# ppc_serial.net
KiCad netlist of a schematic drawn in Altium Designer
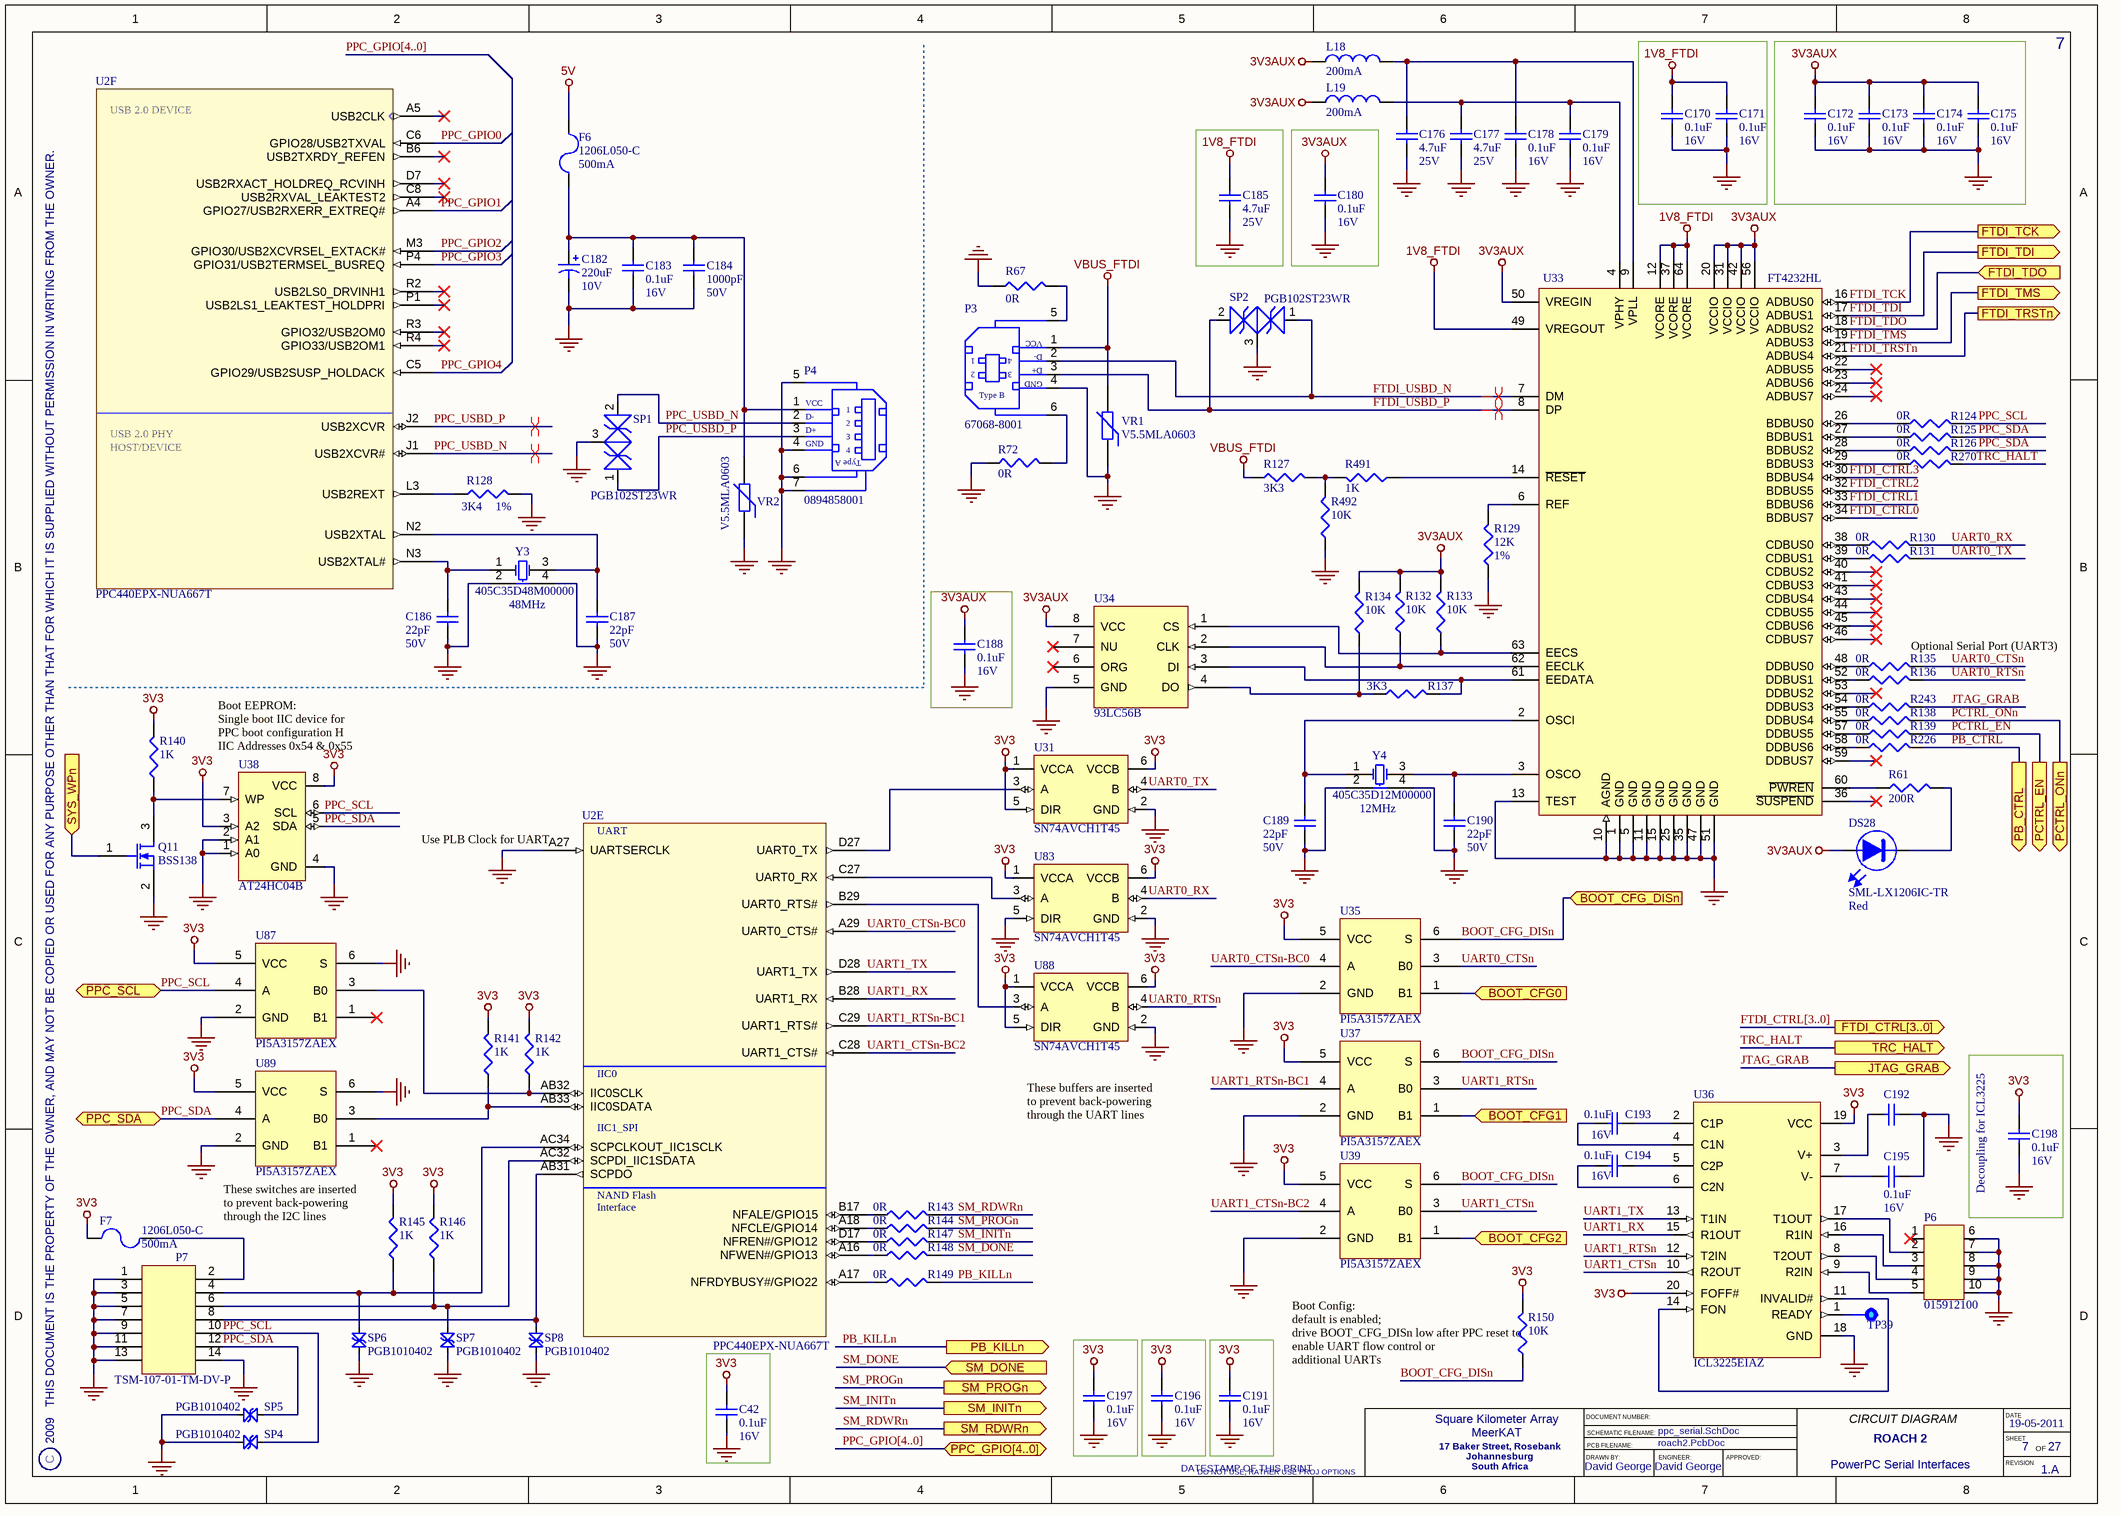
[diagram p0: ppc_serial.SchDoc]

(export (version "E")
  (design (tool "Eeschema 10.0.6"))
  (components
    (comp (ref "C42")
      (value "0.1uF")
      (footprint "CAPC1005X60L")
      (description "0.1uF, Ceramic Capacitor")
      (fields
        (field (name "RATING") "16V")
        (field (name "MANUFACTURER") "VENKEL")
        (field (name "PARTNUM") "C0402X7R160-104KN")
      )
      (libsource (lib "altium_db") (part "CapStd"))
    )
    (comp (ref "C170")
      (value "0.1uF")
      (footprint "CAPC1005X60L")
      (description "0.1uF, Ceramic Capacitor")
      (fields
        (field (name "RATING") "16V")
        (field (name "MANUFACTURER") "VENKEL")
        (field (name "PARTNUM") "C0402X7R160-104KN")
      )
      (libsource (lib "altium_db") (part "CapStd"))
    )
    (comp (ref "C171")
      (value "0.1uF")
      (footprint "CAPC1005X60L")
      (description "0.1uF, Ceramic Capacitor")
      (fields
        (field (name "RATING") "16V")
        (field (name "MANUFACTURER") "VENKEL")
        (field (name "PARTNUM") "C0402X7R160-104KN")
      )
      (libsource (lib "altium_db") (part "CapStd"))
    )
    (comp (ref "C172")
      (value "0.1uF")
      (footprint "CAPC1005X60L")
      (description "0.1uF, Ceramic Capacitor")
      (fields
        (field (name "RATING") "16V")
        (field (name "MANUFACTURER") "VENKEL")
        (field (name "PARTNUM") "C0402X7R160-104KN")
      )
      (libsource (lib "altium_db") (part "CapStd"))
    )
    (comp (ref "C173")
      (value "0.1uF")
      (footprint "CAPC1005X60L")
      (description "0.1uF, Ceramic Capacitor")
      (fields
        (field (name "RATING") "16V")
        (field (name "MANUFACTURER") "VENKEL")
        (field (name "PARTNUM") "C0402X7R160-104KN")
      )
      (libsource (lib "altium_db") (part "CapStd"))
    )
    (comp (ref "C174")
      (value "0.1uF")
      (footprint "CAPC1005X60L")
      (description "0.1uF, Ceramic Capacitor")
      (fields
        (field (name "RATING") "16V")
        (field (name "MANUFACTURER") "VENKEL")
        (field (name "PARTNUM") "C0402X7R160-104KN")
      )
      (libsource (lib "altium_db") (part "CapStd"))
    )
    (comp (ref "C175")
      (value "0.1uF")
      (footprint "CAPC1005X60L")
      (description "0.1uF, Ceramic Capacitor")
      (fields
        (field (name "RATING") "16V")
        (field (name "MANUFACTURER") "VENKEL")
        (field (name "PARTNUM") "C0402X7R160-104KN")
      )
      (libsource (lib "altium_db") (part "CapStd"))
    )
    (comp (ref "C176")
      (value "4.7uF")
      (footprint "CAPC2012X127L")
      (description "4.7uF, Ceramic Capacitor")
      (fields
        (field (name "RATING") "25V")
        (field (name "MANUFACTURER") "MURATA")
        (field (name "PARTNUM") "GRM21BR61E475KA12K")
      )
      (libsource (lib "altium_db") (part "CapStd"))
    )
    (comp (ref "C177")
      (value "4.7uF")
      (footprint "CAPC2012X127L")
      (description "4.7uF, Ceramic Capacitor")
      (fields
        (field (name "RATING") "25V")
        (field (name "MANUFACTURER") "MURATA")
        (field (name "PARTNUM") "GRM21BR61E475KA12K")
      )
      (libsource (lib "altium_db") (part "CapStd"))
    )
    (comp (ref "C178")
      (value "0.1uF")
      (footprint "CAPC1005X60L")
      (description "0.1uF, Ceramic Capacitor")
      (fields
        (field (name "RATING") "16V")
        (field (name "MANUFACTURER") "VENKEL")
        (field (name "PARTNUM") "C0402X7R160-104KN")
      )
      (libsource (lib "altium_db") (part "CapStd"))
    )
    (comp (ref "C179")
      (value "0.1uF")
      (footprint "CAPC1005X60L")
      (description "0.1uF, Ceramic Capacitor")
      (fields
        (field (name "RATING") "16V")
        (field (name "MANUFACTURER") "VENKEL")
        (field (name "PARTNUM") "C0402X7R160-104KN")
      )
      (libsource (lib "altium_db") (part "CapStd"))
    )
    (comp (ref "C180")
      (value "0.1uF")
      (footprint "CAPC1005X60L")
      (description "0.1uF, Ceramic Capacitor")
      (fields
        (field (name "RATING") "16V")
        (field (name "MANUFACTURER") "VENKEL")
        (field (name "PARTNUM") "C0402X7R160-104KN")
      )
      (libsource (lib "altium_db") (part "CapStd"))
    )
    (comp (ref "C182")
      (value "220uF")
      (footprint "CAPMP7343X430L")
      (description "220uF, Solid Tantalum Chip Capacitor")
      (fields
        (field (name "RATING") "10V")
        (field (name "MANUFACTURER") "KEMET")
        (field (name "PARTNUM") "T491X227M010AT")
      )
      (libsource (lib "altium_db") (part "CapPol"))
    )
    (comp (ref "C183")
      (value "0.1uF")
      (footprint "CAPC1005X60L")
      (description "0.1uF, Ceramic Capacitor")
      (fields
        (field (name "RATING") "16V")
        (field (name "MANUFACTURER") "VENKEL")
        (field (name "PARTNUM") "C0402X7R160-104KN")
      )
      (libsource (lib "altium_db") (part "CapStd"))
    )
    (comp (ref "C184")
      (value "1000pF")
      (footprint "CAPC1005X55L")
      (description "1000pF, Ceramic Capacitor")
      (fields
        (field (name "RATING") "50V")
        (field (name "MANUFACTURER") "MURATA")
        (field (name "PARTNUM") "GRM155R61H102KA01D")
      )
      (libsource (lib "altium_db") (part "CapStd"))
    )
    (comp (ref "C185")
      (value "4.7uF")
      (footprint "CAPC2012X127L")
      (description "4.7uF, Ceramic Capacitor")
      (fields
        (field (name "RATING") "25V")
        (field (name "MANUFACTURER") "MURATA")
        (field (name "PARTNUM") "GRM21BR61E475KA12K")
      )
      (libsource (lib "altium_db") (part "CapStd"))
    )
    (comp (ref "C186")
      (value "22pF")
      (footprint "CAPC1005X55L")
      (description "22pF, Ceramic Capacitor")
      (fields
        (field (name "RATING") "50V")
        (field (name "MANUFACTURER") "MURATA")
        (field (name "PARTNUM") "GRM1555C1H220JA01D")
      )
      (libsource (lib "altium_db") (part "CapStd"))
    )
    (comp (ref "C187")
      (value "22pF")
      (footprint "CAPC1005X55L")
      (description "22pF, Ceramic Capacitor")
      (fields
        (field (name "RATING") "50V")
        (field (name "MANUFACTURER") "MURATA")
        (field (name "PARTNUM") "GRM1555C1H220JA01D")
      )
      (libsource (lib "altium_db") (part "CapStd"))
    )
    (comp (ref "C188")
      (value "0.1uF")
      (footprint "CAPC1005X60L")
      (description "0.1uF, Ceramic Capacitor")
      (fields
        (field (name "RATING") "16V")
        (field (name "MANUFACTURER") "VENKEL")
        (field (name "PARTNUM") "C0402X7R160-104KN")
      )
      (libsource (lib "altium_db") (part "CapStd"))
    )
    (comp (ref "C189")
      (value "22pF")
      (footprint "CAPC1005X55L")
      (description "22pF, Ceramic Capacitor")
      (fields
        (field (name "RATING") "50V")
        (field (name "MANUFACTURER") "MURATA")
        (field (name "PARTNUM") "GRM1555C1H220JA01D")
      )
      (libsource (lib "altium_db") (part "CapStd"))
    )
    (comp (ref "C190")
      (value "22pF")
      (footprint "CAPC1005X55L")
      (description "22pF, Ceramic Capacitor")
      (fields
        (field (name "RATING") "50V")
        (field (name "MANUFACTURER") "MURATA")
        (field (name "PARTNUM") "GRM1555C1H220JA01D")
      )
      (libsource (lib "altium_db") (part "CapStd"))
    )
    (comp (ref "C191")
      (value "0.1uF")
      (footprint "CAPC1005X60L")
      (description "0.1uF, Ceramic Capacitor")
      (fields
        (field (name "RATING") "16V")
        (field (name "MANUFACTURER") "VENKEL")
        (field (name "PARTNUM") "C0402X7R160-104KN")
      )
      (libsource (lib "altium_db") (part "CapStd"))
    )
    (comp (ref "C192")
      (value "~")
      (footprint "CAPC1005X60L")
      (description "0.1uF, Ceramic Capacitor")
      (fields (field (name "MANUFACTURER") "VENKEL") (field (name "PARTNUM") "C0402X7R160-104KN"))
      (libsource (lib "altium_db") (part "CapStd"))
    )
    (comp (ref "C193")
      (value "0.1uF")
      (footprint "CAPC1005X60L")
      (description "0.1uF, Ceramic Capacitor")
      (fields
        (field (name "RATING") "16V")
        (field (name "MANUFACTURER") "VENKEL")
        (field (name "PARTNUM") "C0402X7R160-104KN")
      )
      (libsource (lib "altium_db") (part "CapStd"))
    )
    (comp (ref "C194")
      (value "0.1uF")
      (footprint "CAPC1005X60L")
      (description "0.1uF, Ceramic Capacitor")
      (fields
        (field (name "RATING") "16V")
        (field (name "MANUFACTURER") "VENKEL")
        (field (name "PARTNUM") "C0402X7R160-104KN")
      )
      (libsource (lib "altium_db") (part "CapStd"))
    )
    (comp (ref "C195")
      (value "0.1uF")
      (footprint "CAPC1005X60L")
      (description "0.1uF, Ceramic Capacitor")
      (fields
        (field (name "RATING") "16V")
        (field (name "MANUFACTURER") "VENKEL")
        (field (name "PARTNUM") "C0402X7R160-104KN")
      )
      (libsource (lib "altium_db") (part "CapStd"))
    )
    (comp (ref "C196")
      (value "0.1uF")
      (footprint "CAPC1005X60L")
      (description "0.1uF, Ceramic Capacitor")
      (fields
        (field (name "RATING") "16V")
        (field (name "MANUFACTURER") "VENKEL")
        (field (name "PARTNUM") "C0402X7R160-104KN")
      )
      (libsource (lib "altium_db") (part "CapStd"))
    )
    (comp (ref "C197")
      (value "0.1uF")
      (footprint "CAPC1005X60L")
      (description "0.1uF, Ceramic Capacitor")
      (fields
        (field (name "RATING") "16V")
        (field (name "MANUFACTURER") "VENKEL")
        (field (name "PARTNUM") "C0402X7R160-104KN")
      )
      (libsource (lib "altium_db") (part "CapStd"))
    )
    (comp (ref "C198")
      (value "0.1uF")
      (footprint "CAPC1005X60L")
      (description "0.1uF, Ceramic Capacitor")
      (fields
        (field (name "RATING") "16V")
        (field (name "MANUFACTURER") "VENKEL")
        (field (name "PARTNUM") "C0402X7R160-104KN")
      )
      (libsource (lib "altium_db") (part "CapStd"))
    )
    (comp (ref "DS28")
      (value "SML-LX1206IC-TR")
      (footprint "LEDC3216X120N")
      (description "Red, Surface mount, LED, 1206")
      (fields (field (name "COLOUR") "Red") (field (name "MANUFACTURER") "LUMEX"))
      (libsource (lib "altium_db") (part "LEDSTD"))
    )
    (comp (ref "F6")
      (value "1206L050-C")
      (footprint "FUSMC3215X145")
      (description "Resettable, Surface mount Fuse")
      (fields
        (field (name "MANUFACTURER") "Littelfuse")
        (field (name "PARTNUM") "1206L050-C")
        (field (name "RATING") "500mA")
      )
      (libsource (lib "altium_db") (part "FuseStd"))
    )
    (comp (ref "F7")
      (value "1206L050-C")
      (footprint "FUSMC3215X145")
      (description "Resettable, Surface mount Fuse")
      (fields
        (field (name "MANUFACTURER") "Littelfuse")
        (field (name "PARTNUM") "1206L050-C")
        (field (name "RATING") "500mA")
      )
      (libsource (lib "altium_db") (part "FuseStd"))
    )
    (comp (ref "L18")
      (value "600R")
      (footprint "INDC2012X130L")
      (description "600 Ohm, Chip Ferrite Bead")
      (fields
        (field (name "MANUFACTURER") "Murata")
        (field (name "PARTNUM") "BLM21BD601SN1")
        (field (name "RATING") "200mA")
      )
      (libsource (lib "altium_db") (part "IndStd"))
    )
    (comp (ref "L19")
      (value "600R")
      (footprint "INDC2012X130L")
      (description "600 Ohm, Chip Ferrite Bead")
      (fields
        (field (name "MANUFACTURER") "Murata")
        (field (name "PARTNUM") "BLM21BD601SN1")
        (field (name "RATING") "200mA")
      )
      (libsource (lib "altium_db") (part "IndStd"))
    )
    (comp (ref "P3")
      (value "67068-8001")
      (footprint "MOLEX_67068-8001")
      (description "Right angle, Through-hole, USB Type B Receptacle")
      (fields (field (name "PARTNUM") "67068-8001") (field (name "MANUFACTURER") "Molex"))
      (libsource (lib "altium_db") (part "USB_TYPE_B_GENERIC"))
    )
    (comp (ref "P4")
      (value "USB_TYPEA_TYCO")
      (footprint "MOLEX_0894858001")
      (description "Right angle, Through-hole, USB Type A Receptacle")
      (fields (field (name "PARTNUM") "0894858001"))
      (libsource (lib "altium_db") (part "0894858001"))
    )
    (comp (ref "P6")
      (value "015912100")
      (footprint "MOLEX_0015912100")
      (description "2x5, 2.54 mm Pitch, Male Header")
      (fields (field (name "MANUFACTURER") "Molex") (field (name "PARTNUM") "015912100"))
      (libsource (lib "altium_db") (part "con_hdr_2x5"))
    )
    (comp (ref "P7")
      (value "TSM-107-01-TM-DV-P")
      (footprint "SAMTEC_TSM-107-01-TM-DV-P")
      (description "2x7, 2.54 mm Pitch, Male Header")
      (fields (field (name "PARTNUM") "TSM-107-01-TM-DV-P") (field (name "MANUFACTURER") "SAMTEC"))
      (libsource (lib "altium_db") (part "con_hdr_2x7"))
    )
    (comp (ref "Q11")
      (value "BSS138")
      (footprint "SOT95P245X110-3N")
      (description "N-Channel Logic Level Enhancement Mode Field Effect Transistor")
      (fields (field (name "MANUFACTURER") "Fairchild Semiconductor"))
      (libsource (lib "altium_db") (part "BSS138"))
    )
    (comp (ref "R61")
      (value "200R")
      (footprint "RESC1005X40L")
      (description "200R, 1.1mm x 0.5mm, Thick Film Resistor")
      (fields (field (name "MANUFACTURER") "ROYALOHM") (field (name "PARTNUM") "0402WGF0201T1E"))
      (libsource (lib "altium_db") (part "ResStd"))
    )
    (comp (ref "R67")
      (value "0R")
      (footprint "RESC1005X40L")
      (description "0R, 1.1mm x 0.5mm, Thick Film Resistor")
      (fields (field (name "MANUFACTURER") "ROYALOHM") (field (name "PARTNUM") "0402WG00000T1E"))
      (libsource (lib "altium_db") (part "ResStd"))
    )
    (comp (ref "R72")
      (value "0R")
      (footprint "RESC1005X40L")
      (description "0R, 1.1mm x 0.5mm, Thick Film Resistor")
      (fields (field (name "MANUFACTURER") "ROYALOHM") (field (name "PARTNUM") "0402WG00000T1E"))
      (libsource (lib "altium_db") (part "ResStd"))
    )
    (comp (ref "R124")
      (value "0R")
      (footprint "RESC1005X40L")
      (description "0R, 1.1mm x 0.5mm, Thick Film Resistor")
      (fields (field (name "MANUFACTURER") "ROYALOHM") (field (name "PARTNUM") "0402WG00000T1E"))
      (libsource (lib "altium_db") (part "ResStd"))
    )
    (comp (ref "R125")
      (value "0R")
      (footprint "RESC1005X40L")
      (description "0R, 1.1mm x 0.5mm, Thick Film Resistor")
      (fields (field (name "MANUFACTURER") "ROYALOHM") (field (name "PARTNUM") "0402WG00000T1E"))
      (libsource (lib "altium_db") (part "ResStd"))
    )
    (comp (ref "R126")
      (value "0R")
      (footprint "RESC1005X40L")
      (description "0R, 1.1mm x 0.5mm, Thick Film Resistor")
      (fields (field (name "MANUFACTURER") "ROYALOHM") (field (name "PARTNUM") "0402WG00000T1E"))
      (libsource (lib "altium_db") (part "ResStd"))
    )
    (comp (ref "R127")
      (value "3K3")
      (footprint "RESC1005X40L")
      (description "3K3, 1.1mm x 0.5mm, Thick Film Resistor")
      (fields (field (name "MANUFACTURER") "ROYALOHM") (field (name "PARTNUM") "0402WGJ0332T1E"))
      (libsource (lib "altium_db") (part "ResStd"))
    )
    (comp (ref "R128")
      (value "3K4")
      (footprint "RESC1005X40L")
      (description "3K4, 1.1mm x 0.5mm, Thick Film Resistor")
      (fields
        (field (name "MANUFACTURER") "ROYALOHM")
        (field (name "PARTNUM") "0402WGF0342T1E")
        (field (name "TOLERANCE") "1%")
      )
      (libsource (lib "altium_db") (part "ResStd"))
    )
    (comp (ref "R129")
      (value "12K")
      (footprint "RESC1005X40L")
      (description "12K, 1.1mm x 0.5mm, Thick Film Resistor")
      (fields
        (field (name "MANUFACTURER") "ROYALOHM")
        (field (name "PARTNUM") "0402WGF0123T1E")
        (field (name "TOLERANCE") "1%")
      )
      (libsource (lib "altium_db") (part "ResStd"))
    )
    (comp (ref "R130")
      (value "0R")
      (footprint "RESC1005X40L")
      (description "0R, 1.1mm x 0.5mm, Thick Film Resistor")
      (fields (field (name "MANUFACTURER") "ROYALOHM") (field (name "PARTNUM") "0402WG00000T1E"))
      (libsource (lib "altium_db") (part "ResStd"))
    )
    (comp (ref "R131")
      (value "0R")
      (footprint "RESC1005X40L")
      (description "0R, 1.1mm x 0.5mm, Thick Film Resistor")
      (fields (field (name "MANUFACTURER") "ROYALOHM") (field (name "PARTNUM") "0402WG00000T1E"))
      (libsource (lib "altium_db") (part "ResStd"))
    )
    (comp (ref "R132")
      (value "10K")
      (footprint "RESC1005X40L")
      (description "10K, 1.1mm x 0.5mm, Thick Film Resistor")
      (fields (field (name "MANUFACTURER") "ROYALOHM") (field (name "PARTNUM") "0402WGJ0103T1E"))
      (libsource (lib "altium_db") (part "ResStd"))
    )
    (comp (ref "R133")
      (value "10K")
      (footprint "RESC1005X40L")
      (description "10K, 1.1mm x 0.5mm, Thick Film Resistor")
      (fields (field (name "MANUFACTURER") "ROYALOHM") (field (name "PARTNUM") "0402WGJ0103T1E"))
      (libsource (lib "altium_db") (part "ResStd"))
    )
    (comp (ref "R134")
      (value "10K")
      (footprint "RESC1005X40L")
      (description "10K, 1.1mm x 0.5mm, Thick Film Resistor")
      (fields (field (name "MANUFACTURER") "ROYALOHM") (field (name "PARTNUM") "0402WGJ0103T1E"))
      (libsource (lib "altium_db") (part "ResStd"))
    )
    (comp (ref "R135")
      (value "0R")
      (footprint "RESC1005X40L")
      (description "0R, 1.1mm x 0.5mm, Thick Film Resistor")
      (fields (field (name "MANUFACTURER") "ROYALOHM") (field (name "PARTNUM") "0402WG00000T1E"))
      (libsource (lib "altium_db") (part "ResStd"))
    )
    (comp (ref "R136")
      (value "0R")
      (footprint "RESC1005X40L")
      (description "0R, 1.1mm x 0.5mm, Thick Film Resistor")
      (fields (field (name "MANUFACTURER") "ROYALOHM") (field (name "PARTNUM") "0402WG00000T1E"))
      (libsource (lib "altium_db") (part "ResStd"))
    )
    (comp (ref "R137")
      (value "3K3")
      (footprint "RESC1005X40L")
      (description "3K3, 1.1mm x 0.5mm, Thick Film Resistor")
      (fields (field (name "MANUFACTURER") "ROYALOHM") (field (name "PARTNUM") "0402WGJ0332T1E"))
      (libsource (lib "altium_db") (part "ResStd"))
    )
    (comp (ref "R138")
      (value "0R")
      (footprint "RESC1005X40L")
      (description "0R, 1.1mm x 0.5mm, Thick Film Resistor")
      (fields (field (name "MANUFACTURER") "ROYALOHM") (field (name "PARTNUM") "0402WG00000T1E"))
      (libsource (lib "altium_db") (part "ResStd"))
    )
    (comp (ref "R139")
      (value "0R")
      (footprint "RESC1005X40L")
      (description "0R, 1.1mm x 0.5mm, Thick Film Resistor")
      (fields (field (name "MANUFACTURER") "ROYALOHM") (field (name "PARTNUM") "0402WG00000T1E"))
      (libsource (lib "altium_db") (part "ResStd"))
    )
    (comp (ref "R140")
      (value "1K")
      (footprint "RESC1005X40L")
      (description "1K, 1.1mm x 0.5mm, Thick Film Resistor")
      (fields (field (name "MANUFACTURER") "ROYALOHM") (field (name "PARTNUM") "0402WGJ0102T1E"))
      (libsource (lib "altium_db") (part "ResStd"))
    )
    (comp (ref "R141")
      (value "1K")
      (footprint "RESC1005X40L")
      (description "1K, 1.1mm x 0.5mm, Thick Film Resistor")
      (fields (field (name "MANUFACTURER") "ROYALOHM") (field (name "PARTNUM") "0402WGJ0102T1E"))
      (libsource (lib "altium_db") (part "ResStd"))
    )
    (comp (ref "R142")
      (value "1K")
      (footprint "RESC1005X40L")
      (description "1K, 1.1mm x 0.5mm, Thick Film Resistor")
      (fields (field (name "MANUFACTURER") "ROYALOHM") (field (name "PARTNUM") "0402WGJ0102T1E"))
      (libsource (lib "altium_db") (part "ResStd"))
    )
    (comp (ref "R143")
      (value "0R")
      (footprint "RESC1005X40L")
      (description "0R, 1.1mm x 0.5mm, Thick Film Resistor")
      (fields (field (name "MANUFACTURER") "ROYALOHM") (field (name "PARTNUM") "0402WG00000T1E"))
      (libsource (lib "altium_db") (part "ResStd"))
    )
    (comp (ref "R144")
      (value "0R")
      (footprint "RESC1005X40L")
      (description "0R, 1.1mm x 0.5mm, Thick Film Resistor")
      (fields (field (name "MANUFACTURER") "ROYALOHM") (field (name "PARTNUM") "0402WG00000T1E"))
      (libsource (lib "altium_db") (part "ResStd"))
    )
    (comp (ref "R145")
      (value "1K")
      (footprint "RESC1005X40L")
      (description "1K, 1.1mm x 0.5mm, Thick Film Resistor")
      (fields (field (name "MANUFACTURER") "ROYALOHM") (field (name "PARTNUM") "0402WGJ0102T1E"))
      (libsource (lib "altium_db") (part "ResStd"))
    )
    (comp (ref "R146")
      (value "1K")
      (footprint "RESC1005X40L")
      (description "1K, 1.1mm x 0.5mm, Thick Film Resistor")
      (fields (field (name "MANUFACTURER") "ROYALOHM") (field (name "PARTNUM") "0402WGJ0102T1E"))
      (libsource (lib "altium_db") (part "ResStd"))
    )
    (comp (ref "R147")
      (value "0R")
      (footprint "RESC1005X40L")
      (description "0R, 1.1mm x 0.5mm, Thick Film Resistor")
      (fields (field (name "MANUFACTURER") "ROYALOHM") (field (name "PARTNUM") "0402WG00000T1E"))
      (libsource (lib "altium_db") (part "ResStd"))
    )
    (comp (ref "R148")
      (value "0R")
      (footprint "RESC1005X40L")
      (description "0R, 1.1mm x 0.5mm, Thick Film Resistor")
      (fields (field (name "MANUFACTURER") "ROYALOHM") (field (name "PARTNUM") "0402WG00000T1E"))
      (libsource (lib "altium_db") (part "ResStd"))
    )
    (comp (ref "R149")
      (value "0R")
      (footprint "RESC1005X40L")
      (description "0R, 1.1mm x 0.5mm, Thick Film Resistor")
      (fields (field (name "MANUFACTURER") "ROYALOHM") (field (name "PARTNUM") "0402WG00000T1E"))
      (libsource (lib "altium_db") (part "ResStd"))
    )
    (comp (ref "R150")
      (value "10K")
      (footprint "RESC1005X40L")
      (description "10K, 1.1mm x 0.5mm, Thick Film Resistor")
      (fields (field (name "MANUFACTURER") "ROYALOHM") (field (name "PARTNUM") "0402WGJ0103T1E"))
      (libsource (lib "altium_db") (part "ResStd"))
    )
    (comp (ref "R226")
      (value "0R")
      (footprint "RESC1005X40L")
      (description "0R, 1.1mm x 0.5mm, Thick Film Resistor")
      (fields (field (name "MANUFACTURER") "ROYALOHM") (field (name "PARTNUM") "0402WG00000T1E"))
      (libsource (lib "altium_db") (part "ResStd"))
    )
    (comp (ref "R243")
      (value "0R")
      (footprint "RESC1005X40L")
      (description "0R, 1.1mm x 0.5mm, Thick Film Resistor")
      (fields (field (name "MANUFACTURER") "ROYALOHM") (field (name "PARTNUM") "0402WG00000T1E"))
      (libsource (lib "altium_db") (part "ResStd"))
    )
    (comp (ref "R270")
      (value "0R")
      (footprint "RESC1005X40L")
      (description "0R, 1.1mm x 0.5mm, Thick Film Resistor")
      (fields (field (name "MANUFACTURER") "ROYALOHM") (field (name "PARTNUM") "0402WG00000T1E"))
      (libsource (lib "altium_db") (part "ResStd"))
    )
    (comp (ref "R491")
      (value "1K")
      (footprint "RESC1005X40L")
      (description "1K, 1.1mm x 0.5mm, Thick Film Resistor")
      (fields (field (name "MANUFACTURER") "ROYALOHM") (field (name "PARTNUM") "0402WGJ0102T1E"))
      (libsource (lib "altium_db") (part "ResStd"))
    )
    (comp (ref "R492")
      (value "10K")
      (footprint "RESC1005X40L")
      (description "10K, 1.1mm x 0.5mm, Thick Film Resistor")
      (fields (field (name "MANUFACTURER") "ROYALOHM") (field (name "PARTNUM") "0402WGJ0103T1E"))
      (libsource (lib "altium_db") (part "ResStd"))
    )
    (comp (ref "SP1")
      (value "PGB102ST23WR")
      (footprint "SOT95P245X110-3N")
      (description "Ultra-low Capacitance, Surface mount ESD Suppressor")
      (fields (field (name "PARTNUM") "PGB102ST23WR") (field (name "MANUFACTURER") "Littelfuse"))
      (libsource (lib "altium_db") (part "PGB002ST23WR"))
    )
    (comp (ref "SP2")
      (value "PGB102ST23WR")
      (footprint "SOT95P245X110-3N")
      (description "Ultra-low Capacitance, Surface mount ESD Suppressor")
      (fields (field (name "PARTNUM") "PGB102ST23WR") (field (name "MANUFACTURER") "Littelfuse"))
      (libsource (lib "altium_db") (part "PGB002ST23WR"))
    )
    (comp (ref "SP4")
      (value "PGB1010402")
      (footprint "PGB1010402")
      (description "Surface Mount Polymeric ESD Suppressor in an 0402 package")
      (fields (field (name "PARTNUM") "PGB1010402"))
      (libsource (lib "altium_db") (part "PGB1010402"))
    )
    (comp (ref "SP5")
      (value "PGB1010402")
      (footprint "PGB1010402")
      (description "Surface Mount Polymeric ESD Suppressor in an 0402 package")
      (fields (field (name "PARTNUM") "PGB1010402"))
      (libsource (lib "altium_db") (part "PGB1010402"))
    )
    (comp (ref "SP6")
      (value "PGB1010402")
      (footprint "PGB1010402")
      (description "Surface Mount Polymeric ESD Suppressor in an 0402 package")
      (fields (field (name "PARTNUM") "PGB1010402"))
      (libsource (lib "altium_db") (part "PGB1010402"))
    )
    (comp (ref "SP7")
      (value "PGB1010402")
      (footprint "PGB1010402")
      (description "Surface Mount Polymeric ESD Suppressor in an 0402 package")
      (fields (field (name "PARTNUM") "PGB1010402"))
      (libsource (lib "altium_db") (part "PGB1010402"))
    )
    (comp (ref "SP8")
      (value "PGB1010402")
      (footprint "PGB1010402")
      (description "Surface Mount Polymeric ESD Suppressor in an 0402 package")
      (fields (field (name "PARTNUM") "PGB1010402"))
      (libsource (lib "altium_db") (part "PGB1010402"))
    )
    (comp (ref "TP39")
      (value "Testpoint")
      (footprint "TP100")
      (description "1mm Diameter, through-hole, Circular Test-point")
      (libsource (lib "altium_db") (part "Testpoint"))
    )
    (comp (ref "U2")
      (value "PPC440EPX-NUA667T")
      (footprint "TE-PBGA680")
      (description "667MHz, non-RoHS, PPC440EPx uProcessor")
      (fields (field (name "MANUFACTURER") "Applied Micro"))
      (libsource (lib "altium_db") (part "PPC440EPX"))
    )
    (comp (ref "U31")
      (value "SN74AVCH1T45")
      (footprint "SOT23-6")
      (description "Single-Bit Dual Supply Bus Transceiver with Configurable Voltage Translation and 3-State Outputs")
      (fields (field (name "MANUFACTURER") "Texas Instruments"))
      (libsource (lib "altium_db") (part "SN74AVCH1T45"))
    )
    (comp (ref "U33")
      (value "FT4232HL")
      (footprint "QFN64")
      (description "Quad High Speed USB to Multipurpose UART/MPSSE")
      (fields (field (name "MANUFACTURER") "FTDI"))
      (libsource (lib "altium_db") (part "FT4232HL"))
    )
    (comp (ref "U34")
      (value "93LC56B")
      (footprint "SOIC150-8_N")
      (description "2K Microwire Compatible Serial EEPROM")
      (fields (field (name "MANUFACTURER") "Microchip") (field (name "PARTNUM") "93LC56B/SN"))
      (libsource (lib "altium_db") (part "93LC56B"))
    )
    (comp (ref "U35")
      (value "PI5A3157ZAEX")
      (footprint "SC70-6")
      (description "Low voltage SPDT Analogue Switch")
      (fields (field (name "MANUFACTURER") "PERICOM"))
      (libsource (lib "altium_db") (part "PI5A3157ZAEX"))
    )
    (comp (ref "U36")
      (value "ICL3225EIAZ")
      (footprint "SSOP20_M")
      (description "Low-power RS232 transceivers")
      (fields (field (name "MANUFACTURER") "Intersil"))
      (libsource (lib "altium_db") (part "ICL3225"))
    )
    (comp (ref "U37")
      (value "PI5A3157ZAEX")
      (footprint "SC70-6")
      (description "Low voltage SPDT Analogue Switch")
      (fields (field (name "MANUFACTURER") "PERICOM"))
      (libsource (lib "altium_db") (part "PI5A3157ZAEX"))
    )
    (comp (ref "U38")
      (value "AT24HC04B")
      (footprint "TSSOP-8A2")
      (description "4K Serial EEPROM")
      (fields (field (name "MANUFACTURER") "Atmel"))
      (libsource (lib "altium_db") (part "AT24HC04B"))
    )
    (comp (ref "U39")
      (value "PI5A3157ZAEX")
      (footprint "SC70-6")
      (description "Low voltage SPDT Analogue Switch")
      (fields (field (name "MANUFACTURER") "PERICOM"))
      (libsource (lib "altium_db") (part "PI5A3157ZAEX"))
    )
    (comp (ref "U83")
      (value "SN74AVCH1T45")
      (footprint "SOT23-6")
      (description "Single-Bit Dual Supply Bus Transceiver with Configurable Voltage Translation and 3-State Outputs")
      (fields (field (name "MANUFACTURER") "Texas Instruments"))
      (libsource (lib "altium_db") (part "SN74AVCH1T45"))
    )
    (comp (ref "U87")
      (value "PI5A3157ZAEX")
      (footprint "SC70-6")
      (description "Low voltage SPDT Analogue Switch")
      (fields (field (name "MANUFACTURER") "PERICOM"))
      (libsource (lib "altium_db") (part "PI5A3157ZAEX"))
    )
    (comp (ref "U88")
      (value "SN74AVCH1T45")
      (footprint "SOT23-6")
      (description "Single-Bit Dual Supply Bus Transceiver with Configurable Voltage Translation and 3-State Outputs")
      (fields (field (name "MANUFACTURER") "Texas Instruments"))
      (libsource (lib "altium_db") (part "SN74AVCH1T45"))
    )
    (comp (ref "U89")
      (value "PI5A3157ZAEX")
      (footprint "SC70-6")
      (description "Low voltage SPDT Analogue Switch")
      (fields (field (name "MANUFACTURER") "PERICOM"))
      (libsource (lib "altium_db") (part "PI5A3157ZAEX"))
    )
    (comp (ref "VR1")
      (value "V5.5MLA0603")
      (footprint "VAR_V5_5MLA0603")
      (description "Multilayer Transient Voltage Surge Suppressing Varistor")
      (fields (field (name "MANUFACTURER") "Littelfuse") (field (name "PARTNUM") "V5.5MLA0603"))
      (libsource (lib "altium_db") (part "Varistor"))
    )
    (comp (ref "VR2")
      (value "V5.5MLA0603")
      (footprint "VAR_V5_5MLA0603")
      (description "Multilayer Transient Voltage Surge Suppressing Varistor")
      (fields (field (name "MANUFACTURER") "Littelfuse") (field (name "PARTNUM") "V5.5MLA0603"))
      (libsource (lib "altium_db") (part "Varistor"))
    )
    (comp (ref "Y3")
      (value "405XXXXXXMXXXXX")
      (footprint "405XXXXXXMXXXXX")
      (description "48 MHz, Surface mount, Crystal Oscillator")
      (fields (field (name "PARTNUM") "405C35D48M00000") (field (name "FREQUENCY") "48MHz"))
      (libsource (lib "altium_db") (part "405XXXXXXMXXXXX"))
    )
    (comp (ref "Y4")
      (value "405C35D12M00000")
      (footprint "405XXXXXXMXXXXX")
      (description "12 MHz, Surface mount, Crystal Oscillator")
      (fields
        (field (name "PARTNUM") "405C35D12M00000")
        (field (name "FREQUENCY") "12MHz")
        (field (name "MANUFACTURER") "CTS")
      )
      (libsource (lib "altium_db") (part "405XXXXXXMXXXXX"))
    )
  )
  (nets
    (net (code "1") (name "/BOOT_CFG0") (class "Default")
      (node (ref "U35") (pin "1") (pinfunction "B1_1") (pintype "passive"))
    )
    (net (code "2") (name "/BOOT_CFG1") (class "Default")
      (node (ref "U37") (pin "1") (pinfunction "B1_1") (pintype "passive"))
    )
    (net (code "3") (name "/BOOT_CFG2") (class "Default")
      (node (ref "U39") (pin "1") (pinfunction "B1_1") (pintype "passive"))
    )
    (net (code "4") (name "/BOOT_CFG_DISn") (class "Default")
      (node (ref "R150") (pin "1") (pinfunction "1_1") (pintype "passive"))
      (node (ref "U35") (pin "6") (pinfunction "S_6") (pintype "passive"))
      (node (ref "U37") (pin "6") (pinfunction "S_6") (pintype "passive"))
      (node (ref "U39") (pin "6") (pinfunction "S_6") (pintype "passive"))
    )
    (net (code "5") (name "/FTDI_CTRL0") (class "Default")
      (node (ref "U33") (pin "34") (pinfunction "BDBUS7_34") (pintype "bidirectional"))
    )
    (net (code "6") (name "/FTDI_CTRL1") (class "Default")
      (node (ref "U33") (pin "33") (pinfunction "BDBUS6_33") (pintype "bidirectional"))
    )
    (net (code "7") (name "/FTDI_CTRL2") (class "Default")
      (node (ref "U33") (pin "32") (pinfunction "BDBUS5_32") (pintype "bidirectional"))
    )
    (net (code "8") (name "/FTDI_CTRL3") (class "Default")
      (node (ref "U33") (pin "30") (pinfunction "BDBUS4_30") (pintype "bidirectional"))
    )
    (net (code "10") (name "/FTDI_TCK") (class "Default")
      (node (ref "U33") (pin "16") (pinfunction "ADBUS0_16") (pintype "bidirectional"))
    )
    (net (code "11") (name "/FTDI_TDI") (class "Default")
      (node (ref "U33") (pin "17") (pinfunction "ADBUS1_17") (pintype "bidirectional"))
    )
    (net (code "12") (name "/FTDI_TDO") (class "Default")
      (node (ref "U33") (pin "18") (pinfunction "ADBUS2_18") (pintype "bidirectional"))
    )
    (net (code "13") (name "/FTDI_TMS") (class "Default")
      (node (ref "U33") (pin "19") (pinfunction "ADBUS3_19") (pintype "bidirectional"))
    )
    (net (code "14") (name "/FTDI_TRSTn") (class "Default")
      (node (ref "U33") (pin "21") (pinfunction "ADBUS4_21") (pintype "bidirectional"))
    )
    (net (code "15") (name "/FTDI_USBD_N") (class "Default")
      (node (ref "P3") (pin "2") (pinfunction "2_2") (pintype "bidirectional"))
      (node (ref "SP2") (pin "1") (pinfunction "A_1") (pintype "passive"))
      (node (ref "U33") (pin "7") (pinfunction "DM_7") (pintype "passive"))
    )
    (net (code "16") (name "/FTDI_USBD_P") (class "Default")
      (node (ref "P3") (pin "3") (pinfunction "3_3") (pintype "bidirectional"))
      (node (ref "SP2") (pin "2") (pinfunction "B_2") (pintype "passive"))
      (node (ref "U33") (pin "8") (pinfunction "DP_8") (pintype "passive"))
    )
    (net (code "17") (name "/JTAG_GRAB") (class "Default")
      (node (ref "R243") (pin "2") (pinfunction "2_2") (pintype "passive"))
    )
    (net (code "18") (name "/PB_CTRL") (class "Default")
      (node (ref "R226") (pin "2") (pinfunction "2_2") (pintype "passive"))
    )
    (net (code "19") (name "/PB_KILLn") (class "Default")
      (node (ref "R149") (pin "2") (pinfunction "2_2") (pintype "passive"))
    )
    (net (code "20") (name "/PCTRL_EN") (class "Default")
      (node (ref "R139") (pin "2") (pinfunction "2_2") (pintype "passive"))
    )
    (net (code "21") (name "/PCTRL_ONn") (class "Default")
      (node (ref "R138") (pin "2") (pinfunction "2_2") (pintype "passive"))
    )
    (net (code "22") (name "/PPC_GPIO0") (class "Default")
      (node (ref "U2") (pin "C6") (pinfunction "GPIO28/USB2TXVAL_C6") (pintype "input"))
    )
    (net (code "23") (name "/PPC_GPIO1") (class "Default")
      (node (ref "U2") (pin "A4") (pinfunction "GPIO27/USB2RXERR_EXTREQ#_A4") (pintype "output"))
    )
    (net (code "24") (name "/PPC_GPIO2") (class "Default")
      (node (ref "U2") (pin "M3") (pinfunction "GPIO30/USB2XCVRSEL_EXTACK#_M3") (pintype "input"))
    )
    (net (code "25") (name "/PPC_GPIO3") (class "Default")
      (node (ref "U2") (pin "P4") (pinfunction "GPIO31/USB2TERMSEL_BUSREQ_P4") (pintype "input"))
    )
    (net (code "26") (name "/PPC_GPIO4") (class "Default")
      (node (ref "U2") (pin "C5") (pinfunction "GPIO29/USB2SUSP_HOLDACK_C5") (pintype "input"))
    )
    (net (code "28") (name "/PPC_SCL") (class "Default")
      (node (ref "P7") (pin "10") (pinfunction "10_10") (pintype "passive"))
      (node (ref "R124") (pin "2") (pinfunction "2_2") (pintype "passive"))
      (node (ref "SP4") (pin "1") (pinfunction "A_1") (pintype "passive"))
      (node (ref "U38") (pin "6") (pinfunction "SCL_6") (pintype "bidirectional"))
      (node (ref "U87") (pin "4") (pinfunction "A_4") (pintype "passive"))
    )
    (net (code "29") (name "/PPC_SDA") (class "Default")
      (node (ref "P7") (pin "12") (pinfunction "12_12") (pintype "passive"))
      (node (ref "R125") (pin "2") (pinfunction "2_2") (pintype "passive"))
      (node (ref "R126") (pin "2") (pinfunction "2_2") (pintype "passive"))
      (node (ref "SP5") (pin "1") (pinfunction "A_1") (pintype "passive"))
      (node (ref "U38") (pin "5") (pinfunction "SDA_5") (pintype "bidirectional"))
      (node (ref "U89") (pin "4") (pinfunction "A_4") (pintype "passive"))
    )
    (net (code "30") (name "/PPC_USBD_N") (class "Default")
      (node (ref "P4") (pin "2") (pinfunction "2_2") (pintype "bidirectional"))
      (node (ref "SP1") (pin "2") (pinfunction "B_2") (pintype "passive"))
      (node (ref "U2") (pin "J1") (pinfunction "USB2XCVR#_J1") (pintype "bidirectional"))
    )
    (net (code "31") (name "/PPC_USBD_P") (class "Default")
      (node (ref "P4") (pin "3") (pinfunction "3_3") (pintype "bidirectional"))
      (node (ref "SP1") (pin "1") (pinfunction "A_1") (pintype "passive"))
      (node (ref "U2") (pin "J2") (pinfunction "USB2XCVR_J2") (pintype "bidirectional"))
    )
    (net (code "32") (name "/SM_DONE") (class "Default")
      (node (ref "R148") (pin "2") (pinfunction "2_2") (pintype "passive"))
    )
    (net (code "33") (name "/SM_INITn") (class "Default")
      (node (ref "R147") (pin "2") (pinfunction "2_2") (pintype "passive"))
    )
    (net (code "34") (name "/SM_PROGn") (class "Default")
      (node (ref "R144") (pin "2") (pinfunction "2_2") (pintype "passive"))
    )
    (net (code "35") (name "/SM_RDWRn") (class "Default")
      (node (ref "R143") (pin "2") (pinfunction "2_2") (pintype "passive"))
    )
    (net (code "36") (name "/SYS_WPn") (class "Default")
      (node (ref "Q11") (pin "1") (pinfunction "G_1") (pintype "passive"))
    )
    (net (code "37") (name "/TRC_HALT") (class "Default")
      (node (ref "R270") (pin "2") (pinfunction "2_2") (pintype "passive"))
    )
    (net (code "38") (name "/UART0_CTSn") (class "Default")
      (node (ref "R135") (pin "2") (pinfunction "2_2") (pintype "passive"))
      (node (ref "U35") (pin "3") (pinfunction "B0_3") (pintype "passive"))
    )
    (net (code "39") (name "/UART0_CTSn-BC0") (class "Default")
      (node (ref "U2") (pin "A29") (pinfunction "UART0_CTS#_A29") (pintype "input"))
      (node (ref "U35") (pin "4") (pinfunction "A_4") (pintype "passive"))
    )
    (net (code "40") (name "/UART0_RTSn") (class "Default")
      (node (ref "R136") (pin "2") (pinfunction "2_2") (pintype "passive"))
      (node (ref "U88") (pin "4") (pinfunction "B_4") (pintype "bidirectional"))
    )
    (net (code "41") (name "/UART0_RX") (class "Default")
      (node (ref "R130") (pin "2") (pinfunction "2_2") (pintype "passive"))
      (node (ref "U83") (pin "4") (pinfunction "B_4") (pintype "bidirectional"))
    )
    (net (code "42") (name "/UART0_TX") (class "Default")
      (node (ref "R131") (pin "2") (pinfunction "2_2") (pintype "passive"))
      (node (ref "U31") (pin "4") (pinfunction "B_4") (pintype "bidirectional"))
    )
    (net (code "43") (name "/UART1_CTSn") (class "Default")
      (node (ref "U36") (pin "10") (pinfunction "R2OUT_10") (pintype "output"))
      (node (ref "U39") (pin "3") (pinfunction "B0_3") (pintype "passive"))
    )
    (net (code "44") (name "/UART1_CTSn-BC2") (class "Default")
      (node (ref "U2") (pin "C28") (pinfunction "UART1_CTS#_C28") (pintype "input"))
      (node (ref "U39") (pin "4") (pinfunction "A_4") (pintype "passive"))
    )
    (net (code "45") (name "/UART1_RTSn") (class "Default")
      (node (ref "U36") (pin "12") (pinfunction "T2IN_12") (pintype "input"))
      (node (ref "U37") (pin "3") (pinfunction "B0_3") (pintype "passive"))
    )
    (net (code "46") (name "/UART1_RTSn-BC1") (class "Default")
      (node (ref "U2") (pin "C29") (pinfunction "UART1_RTS#_C29") (pintype "output"))
      (node (ref "U37") (pin "4") (pinfunction "A_4") (pintype "passive"))
    )
    (net (code "47") (name "/UART1_RX") (class "Default")
      (node (ref "U2") (pin "B28") (pinfunction "UART1_RX_B28") (pintype "input"))
      (node (ref "U36") (pin "15") (pinfunction "R1OUT_15") (pintype "output"))
    )
    (net (code "48") (name "/UART1_TX") (class "Default")
      (node (ref "U2") (pin "D28") (pinfunction "UART1_TX_D28") (pintype "output"))
      (node (ref "U36") (pin "13") (pinfunction "T1IN_13") (pintype "input"))
    )
    (net (code "49") (name "1V8_FTDI") (class "Default")
      (node (ref "C170") (pin "2") (pinfunction "2_2") (pintype "passive"))
      (node (ref "C171") (pin "2") (pinfunction "2_2") (pintype "passive"))
      (node (ref "C185") (pin "2") (pinfunction "2_2") (pintype "passive"))
      (node (ref "U33") (pin "12") (pinfunction "VCORE_12") (pintype "passive"))
      (node (ref "U33") (pin "37") (pinfunction "VCORE_37") (pintype "passive"))
      (node (ref "U33") (pin "49") (pinfunction "VREGOUT_49") (pintype "passive"))
      (node (ref "U33") (pin "64") (pinfunction "VCORE_64") (pintype "passive"))
    )
    (net (code "50") (name "3V3") (class "Default")
      (node (ref "C191") (pin "2") (pinfunction "2_2") (pintype "passive"))
      (node (ref "C196") (pin "2") (pinfunction "2_2") (pintype "passive"))
      (node (ref "C197") (pin "2") (pinfunction "2_2") (pintype "passive"))
      (node (ref "C198") (pin "2") (pinfunction "2_2") (pintype "passive"))
      (node (ref "C42") (pin "2") (pinfunction "2_2") (pintype "passive"))
      (node (ref "F7") (pin "2") (pinfunction "2_2") (pintype "passive"))
      (node (ref "R140") (pin "2") (pinfunction "2_2") (pintype "passive"))
      (node (ref "R141") (pin "2") (pinfunction "2_2") (pintype "passive"))
      (node (ref "R142") (pin "2") (pinfunction "2_2") (pintype "passive"))
      (node (ref "R145") (pin "2") (pinfunction "2_2") (pintype "passive"))
      (node (ref "R146") (pin "2") (pinfunction "2_2") (pintype "passive"))
      (node (ref "R150") (pin "2") (pinfunction "2_2") (pintype "passive"))
      (node (ref "U31") (pin "1") (pinfunction "VCCA_1") (pintype "power_in"))
      (node (ref "U31") (pin "5") (pinfunction "DIR_5") (pintype "input"))
      (node (ref "U31") (pin "6") (pinfunction "VCCB_6") (pintype "power_in"))
      (node (ref "U35") (pin "5") (pinfunction "VCC_5") (pintype "passive"))
      (node (ref "U36") (pin "19") (pinfunction "VCC_19") (pintype "passive"))
      (node (ref "U36") (pin "20") (pinfunction "FOFF#_20") (pintype "input"))
      (node (ref "U37") (pin "5") (pinfunction "VCC_5") (pintype "passive"))
      (node (ref "U38") (pin "3") (pinfunction "A2_3") (pintype "input"))
      (node (ref "U38") (pin "8") (pinfunction "VCC_8") (pintype "passive"))
      (node (ref "U39") (pin "5") (pinfunction "VCC_5") (pintype "passive"))
      (node (ref "U83") (pin "1") (pinfunction "VCCA_1") (pintype "power_in"))
      (node (ref "U83") (pin "6") (pinfunction "VCCB_6") (pintype "power_in"))
      (node (ref "U87") (pin "5") (pinfunction "VCC_5") (pintype "passive"))
      (node (ref "U88") (pin "1") (pinfunction "VCCA_1") (pintype "power_in"))
      (node (ref "U88") (pin "5") (pinfunction "DIR_5") (pintype "input"))
      (node (ref "U88") (pin "6") (pinfunction "VCCB_6") (pintype "power_in"))
      (node (ref "U89") (pin "5") (pinfunction "VCC_5") (pintype "passive"))
    )
    (net (code "51") (name "3V3AUX") (class "Default")
      (node (ref "C172") (pin "2") (pinfunction "2_2") (pintype "passive"))
      (node (ref "C173") (pin "2") (pinfunction "2_2") (pintype "passive"))
      (node (ref "C174") (pin "2") (pinfunction "2_2") (pintype "passive"))
      (node (ref "C175") (pin "2") (pinfunction "2_2") (pintype "passive"))
      (node (ref "C180") (pin "2") (pinfunction "2_2") (pintype "passive"))
      (node (ref "C188") (pin "2") (pinfunction "2_2") (pintype "passive"))
      (node (ref "DS28") (pin "2") (pinfunction "A_2") (pintype "passive"))
      (node (ref "L18") (pin "1") (pinfunction "1_1") (pintype "passive"))
      (node (ref "L19") (pin "1") (pinfunction "1_1") (pintype "passive"))
      (node (ref "R132") (pin "2") (pinfunction "2_2") (pintype "passive"))
      (node (ref "R133") (pin "2") (pinfunction "2_2") (pintype "passive"))
      (node (ref "R134") (pin "2") (pinfunction "2_2") (pintype "passive"))
      (node (ref "U33") (pin "20") (pinfunction "VCCIO_20") (pintype "passive"))
      (node (ref "U33") (pin "31") (pinfunction "VCCIO_31") (pintype "passive"))
      (node (ref "U33") (pin "42") (pinfunction "VCCIO_42") (pintype "passive"))
      (node (ref "U33") (pin "50") (pinfunction "VREGIN_50") (pintype "passive"))
      (node (ref "U33") (pin "56") (pinfunction "VCCIO_56") (pintype "passive"))
      (node (ref "U34") (pin "8") (pinfunction "VCC_8") (pintype "power_in"))
    )
    (net (code "52") (name "5V") (class "Default")
      (node (ref "F6") (pin "2") (pinfunction "2_2") (pintype "passive"))
    )
    (net (code "53") (name "GND") (class "Default")
      (node (ref "C170") (pin "1") (pinfunction "1_1") (pintype "passive"))
      (node (ref "C171") (pin "1") (pinfunction "1_1") (pintype "passive"))
      (node (ref "C172") (pin "1") (pinfunction "1_1") (pintype "passive"))
      (node (ref "C173") (pin "1") (pinfunction "1_1") (pintype "passive"))
      (node (ref "C174") (pin "1") (pinfunction "1_1") (pintype "passive"))
      (node (ref "C175") (pin "1") (pinfunction "1_1") (pintype "passive"))
      (node (ref "C176") (pin "1") (pinfunction "1_1") (pintype "passive"))
      (node (ref "C177") (pin "1") (pinfunction "1_1") (pintype "passive"))
      (node (ref "C178") (pin "1") (pinfunction "1_1") (pintype "passive"))
      (node (ref "C179") (pin "1") (pinfunction "1_1") (pintype "passive"))
      (node (ref "C180") (pin "1") (pinfunction "1_1") (pintype "passive"))
      (node (ref "C182") (pin "2") (pinfunction "2_2") (pintype "passive"))
      (node (ref "C183") (pin "1") (pinfunction "1_1") (pintype "passive"))
      (node (ref "C184") (pin "1") (pinfunction "1_1") (pintype "passive"))
      (node (ref "C185") (pin "1") (pinfunction "1_1") (pintype "passive"))
      (node (ref "C186") (pin "1") (pinfunction "1_1") (pintype "passive"))
      (node (ref "C187") (pin "1") (pinfunction "1_1") (pintype "passive"))
      (node (ref "C188") (pin "1") (pinfunction "1_1") (pintype "passive"))
      (node (ref "C189") (pin "1") (pinfunction "1_1") (pintype "passive"))
      (node (ref "C190") (pin "1") (pinfunction "1_1") (pintype "passive"))
      (node (ref "C191") (pin "1") (pinfunction "1_1") (pintype "passive"))
      (node (ref "C192") (pin "1") (pinfunction "1_1") (pintype "passive"))
      (node (ref "C195") (pin "1") (pinfunction "1_1") (pintype "passive"))
      (node (ref "C196") (pin "1") (pinfunction "1_1") (pintype "passive"))
      (node (ref "C197") (pin "1") (pinfunction "1_1") (pintype "passive"))
      (node (ref "C198") (pin "1") (pinfunction "1_1") (pintype "passive"))
      (node (ref "C42") (pin "1") (pinfunction "1_1") (pintype "passive"))
      (node (ref "P3") (pin "4") (pinfunction "4_4") (pintype "power_in"))
      (node (ref "P4") (pin "4") (pinfunction "4_4") (pintype "power_in"))
      (node (ref "P4") (pin "5") (pinfunction "5_5") (pintype "power_in"))
      (node (ref "P4") (pin "6") (pinfunction "6_6") (pintype "power_in"))
      (node (ref "P4") (pin "7") (pinfunction "7_7") (pintype "power_in"))
      (node (ref "P6") (pin "10") (pinfunction "10_10") (pintype "passive"))
      (node (ref "P6") (pin "6") (pinfunction "6_6") (pintype "passive"))
      (node (ref "P6") (pin "7") (pinfunction "7_7") (pintype "passive"))
      (node (ref "P6") (pin "8") (pinfunction "8_8") (pintype "passive"))
      (node (ref "P6") (pin "9") (pinfunction "9_9") (pintype "passive"))
      (node (ref "P7") (pin "1") (pinfunction "1_1") (pintype "passive"))
      (node (ref "P7") (pin "11") (pinfunction "11_11") (pintype "passive"))
      (node (ref "P7") (pin "13") (pinfunction "13_13") (pintype "passive"))
      (node (ref "P7") (pin "14") (pinfunction "14_14") (pintype "passive"))
      (node (ref "P7") (pin "3") (pinfunction "3_3") (pintype "passive"))
      (node (ref "P7") (pin "5") (pinfunction "5_5") (pintype "passive"))
      (node (ref "P7") (pin "7") (pinfunction "7_7") (pintype "passive"))
      (node (ref "P7") (pin "9") (pinfunction "9_9") (pintype "passive"))
      (node (ref "Q11") (pin "2") (pinfunction "S_2") (pintype "passive"))
      (node (ref "R128") (pin "2") (pinfunction "2_2") (pintype "passive"))
      (node (ref "R129") (pin "1") (pinfunction "1_1") (pintype "passive"))
      (node (ref "R492") (pin "1") (pinfunction "1_1") (pintype "passive"))
      (node (ref "R67") (pin "1") (pinfunction "1_1") (pintype "passive"))
      (node (ref "R72") (pin "1") (pinfunction "1_1") (pintype "passive"))
      (node (ref "SP1") (pin "3") (pinfunction "COM_3") (pintype "passive"))
      (node (ref "SP2") (pin "3") (pinfunction "COM_3") (pintype "passive"))
      (node (ref "SP4") (pin "2") (pinfunction "B_2") (pintype "passive"))
      (node (ref "SP5") (pin "2") (pinfunction "B_2") (pintype "passive"))
      (node (ref "SP6") (pin "1") (pinfunction "A_1") (pintype "passive"))
      (node (ref "SP7") (pin "1") (pinfunction "A_1") (pintype "passive"))
      (node (ref "SP8") (pin "1") (pinfunction "A_1") (pintype "passive"))
      (node (ref "U2") (pin "A27") (pinfunction "UARTSERCLK_A27") (pintype "input"))
      (node (ref "U31") (pin "2") (pinfunction "GND_2") (pintype "input"))
      (node (ref "U33") (pin "1") (pinfunction "GND_1") (pintype "passive"))
      (node (ref "U33") (pin "10") (pinfunction "AGND_10") (pintype "input"))
      (node (ref "U33") (pin "11") (pinfunction "GND_11") (pintype "passive"))
      (node (ref "U33") (pin "13") (pinfunction "TEST_13") (pintype "passive"))
      (node (ref "U33") (pin "15") (pinfunction "GND_15") (pintype "passive"))
      (node (ref "U33") (pin "25") (pinfunction "GND_25") (pintype "passive"))
      (node (ref "U33") (pin "35") (pinfunction "GND_35") (pintype "passive"))
      (node (ref "U33") (pin "47") (pinfunction "GND_47") (pintype "passive"))
      (node (ref "U33") (pin "5") (pinfunction "GND_5") (pintype "passive"))
      (node (ref "U33") (pin "51") (pinfunction "GND_51") (pintype "passive"))
      (node (ref "U34") (pin "5") (pinfunction "GND_5") (pintype "power_in"))
      (node (ref "U35") (pin "2") (pinfunction "GND_2") (pintype "passive"))
      (node (ref "U36") (pin "18") (pinfunction "GND_18") (pintype "passive"))
      (node (ref "U37") (pin "2") (pinfunction "GND_2") (pintype "passive"))
      (node (ref "U38") (pin "1") (pinfunction "A0_1") (pintype "input"))
      (node (ref "U38") (pin "2") (pinfunction "A1_2") (pintype "input"))
      (node (ref "U38") (pin "4") (pinfunction "GND_4") (pintype "passive"))
      (node (ref "U39") (pin "2") (pinfunction "GND_2") (pintype "passive"))
      (node (ref "U83") (pin "2") (pinfunction "GND_2") (pintype "input"))
      (node (ref "U83") (pin "5") (pinfunction "DIR_5") (pintype "input"))
      (node (ref "U87") (pin "2") (pinfunction "GND_2") (pintype "passive"))
      (node (ref "U87") (pin "6") (pinfunction "S_6") (pintype "passive"))
      (node (ref "U88") (pin "2") (pinfunction "GND_2") (pintype "input"))
      (node (ref "U89") (pin "2") (pinfunction "GND_2") (pintype "passive"))
      (node (ref "U89") (pin "6") (pinfunction "S_6") (pintype "passive"))
      (node (ref "VR1") (pin "1") (pinfunction "1_1") (pintype "passive"))
      (node (ref "VR2") (pin "1") (pinfunction "1_1") (pintype "passive"))
      (node (ref "Y3") (pin "2") (pinfunction "2_2") (pintype "passive"))
      (node (ref "Y3") (pin "4") (pinfunction "4_4") (pintype "passive"))
      (node (ref "Y4") (pin "2") (pinfunction "2_2") (pintype "passive"))
      (node (ref "Y4") (pin "4") (pinfunction "4_4") (pintype "passive"))
    )
    (net (code "54") (name "Net-(C182-Pad1)") (class "Default")
      (node (ref "C182") (pin "1") (pinfunction "1_1") (pintype "passive"))
      (node (ref "C183") (pin "2") (pinfunction "2_2") (pintype "passive"))
      (node (ref "C184") (pin "2") (pinfunction "2_2") (pintype "passive"))
      (node (ref "F6") (pin "1") (pinfunction "1_1") (pintype "passive"))
      (node (ref "P4") (pin "1") (pinfunction "1_1") (pintype "power_in"))
      (node (ref "VR2") (pin "2") (pinfunction "2_2") (pintype "passive"))
    )
    (net (code "55") (name "Net-(DS28-K)") (class "Default")
      (node (ref "DS28") (pin "1") (pinfunction "K_1") (pintype "passive"))
      (node (ref "R61") (pin "2") (pinfunction "2_2") (pintype "passive"))
    )
    (net (code "56") (name "Net-(F7-Pad1)") (class "Default")
      (node (ref "F7") (pin "1") (pinfunction "1_1") (pintype "passive"))
      (node (ref "P7") (pin "2") (pinfunction "2_2") (pintype "passive"))
    )
    (net (code "57") (name "Net-(P3-Pad5)") (class "Default")
      (node (ref "P3") (pin "5") (pinfunction "5_5") (pintype "power_in"))
      (node (ref "R67") (pin "2") (pinfunction "2_2") (pintype "passive"))
    )
    (net (code "58") (name "Net-(P3-Pad6)") (class "Default")
      (node (ref "P3") (pin "6") (pinfunction "6_6") (pintype "power_in"))
      (node (ref "R72") (pin "2") (pinfunction "2_2") (pintype "passive"))
    )
    (net (code "59") (name "Net-(Q11-D)") (class "Default")
      (node (ref "Q11") (pin "3") (pinfunction "D_3") (pintype "passive"))
      (node (ref "R140") (pin "1") (pinfunction "1_1") (pintype "passive"))
      (node (ref "U38") (pin "7") (pinfunction "WP_7") (pintype "input"))
    )
    (net (code "60") (name "Net-(R127-Pad2)") (class "Default")
      (node (ref "R127") (pin "2") (pinfunction "2_2") (pintype "passive"))
      (node (ref "R491") (pin "2") (pinfunction "2_2") (pintype "passive"))
      (node (ref "R492") (pin "2") (pinfunction "2_2") (pintype "passive"))
    )
    (net (code "61") (name "Net-(SP6-B)") (class "Default")
      (node (ref "P7") (pin "4") (pinfunction "4_4") (pintype "passive"))
      (node (ref "R145") (pin "1") (pinfunction "1_1") (pintype "passive"))
      (node (ref "SP6") (pin "2") (pinfunction "B_2") (pintype "passive"))
      (node (ref "U2") (pin "AC34") (pinfunction "SCPCLKOUT_IIC1SCLK_AC34") (pintype "bidirectional"))
    )
    (net (code "62") (name "Net-(SP7-B)") (class "Default")
      (node (ref "P7") (pin "6") (pinfunction "6_6") (pintype "passive"))
      (node (ref "R146") (pin "1") (pinfunction "1_1") (pintype "passive"))
      (node (ref "SP7") (pin "2") (pinfunction "B_2") (pintype "passive"))
      (node (ref "U2") (pin "AC32") (pinfunction "SCPDI_IIC1SDATA_AC32") (pintype "bidirectional"))
    )
    (net (code "63") (name "Net-(SP8-B)") (class "Default")
      (node (ref "P7") (pin "8") (pinfunction "8_8") (pintype "passive"))
      (node (ref "SP8") (pin "2") (pinfunction "B_2") (pintype "passive"))
      (node (ref "U2") (pin "AB31") (pinfunction "SCPDO_AB31") (pintype "output"))
    )
    (net (code "64") (name "Net-(U2E-IIC0SCLK)") (class "Default")
      (node (ref "R142") (pin "1") (pinfunction "1_1") (pintype "passive"))
      (node (ref "U2") (pin "AB32") (pinfunction "IIC0SCLK_AB32") (pintype "bidirectional"))
      (node (ref "U87") (pin "3") (pinfunction "B0_3") (pintype "passive"))
    )
    (net (code "65") (name "Net-(U2E-IIC0SDATA)") (class "Default")
      (node (ref "R141") (pin "1") (pinfunction "1_1") (pintype "passive"))
      (node (ref "U2") (pin "AB33") (pinfunction "IIC0SDATA_AB33") (pintype "bidirectional"))
      (node (ref "U89") (pin "3") (pinfunction "B0_3") (pintype "passive"))
    )
    (net (code "66") (name "Net-(U2E-NFALE{slash}GPIO15)") (class "Default")
      (node (ref "R143") (pin "1") (pinfunction "1_1") (pintype "passive"))
      (node (ref "U2") (pin "B17") (pinfunction "NFALE/GPIO15_B17") (pintype "bidirectional"))
    )
    (net (code "67") (name "Net-(U2E-NFCLE{slash}GPIO14)") (class "Default")
      (node (ref "R144") (pin "1") (pinfunction "1_1") (pintype "passive"))
      (node (ref "U2") (pin "A18") (pinfunction "NFCLE/GPIO14_A18") (pintype "bidirectional"))
    )
    (net (code "68") (name "Net-(U2E-NFRDYBUSY#{slash}GPIO22)") (class "Default")
      (node (ref "R149") (pin "1") (pinfunction "1_1") (pintype "passive"))
      (node (ref "U2") (pin "A17") (pinfunction "NFRDYBUSY#/GPIO22_A17") (pintype "bidirectional"))
    )
    (net (code "69") (name "Net-(U2E-NFREN#{slash}GPIO12)") (class "Default")
      (node (ref "R147") (pin "1") (pinfunction "1_1") (pintype "passive"))
      (node (ref "U2") (pin "D17") (pinfunction "NFREN#/GPIO12_D17") (pintype "bidirectional"))
    )
    (net (code "70") (name "Net-(U2E-NFWEN#{slash}GPIO13)") (class "Default")
      (node (ref "R148") (pin "1") (pinfunction "1_1") (pintype "passive"))
      (node (ref "U2") (pin "A16") (pinfunction "NFWEN#/GPIO13_A16") (pintype "bidirectional"))
    )
    (net (code "71") (name "Net-(U2E-UART0_RTS#)") (class "Default")
      (node (ref "U2") (pin "B29") (pinfunction "UART0_RTS#_B29") (pintype "output"))
      (node (ref "U88") (pin "3") (pinfunction "A_3") (pintype "bidirectional"))
    )
    (net (code "72") (name "Net-(U2E-UART0_RX)") (class "Default")
      (node (ref "U2") (pin "C27") (pinfunction "UART0_RX_C27") (pintype "input"))
      (node (ref "U83") (pin "3") (pinfunction "A_3") (pintype "bidirectional"))
    )
    (net (code "73") (name "Net-(U2E-UART0_TX)") (class "Default")
      (node (ref "U2") (pin "D27") (pinfunction "UART0_TX_D27") (pintype "output"))
      (node (ref "U31") (pin "3") (pinfunction "A_3") (pintype "bidirectional"))
    )
    (net (code "74") (name "Net-(U2F-USB2REXT)") (class "Default")
      (node (ref "R128") (pin "1") (pinfunction "1_1") (pintype "passive"))
      (node (ref "U2") (pin "L3") (pinfunction "USB2REXT_L3") (pintype "output"))
    )
    (net (code "75") (name "Net-(U2F-USB2XTAL#)") (class "Default")
      (node (ref "C186") (pin "2") (pinfunction "2_2") (pintype "passive"))
      (node (ref "U2") (pin "N3") (pinfunction "USB2XTAL#_N3") (pintype "output"))
      (node (ref "Y3") (pin "1") (pinfunction "1_1") (pintype "passive"))
    )
    (net (code "76") (name "Net-(U2F-USB2XTAL)") (class "Default")
      (node (ref "C187") (pin "2") (pinfunction "2_2") (pintype "passive"))
      (node (ref "U2") (pin "N2") (pinfunction "USB2XTAL_N2") (pintype "output"))
      (node (ref "Y3") (pin "3") (pinfunction "3_3") (pintype "passive"))
    )
    (net (code "77") (name "Net-(U33-BDBUS0)") (class "Default")
      (node (ref "R124") (pin "1") (pinfunction "1_1") (pintype "passive"))
      (node (ref "U33") (pin "26") (pinfunction "BDBUS0_26") (pintype "bidirectional"))
    )
    (net (code "78") (name "Net-(U33-BDBUS1)") (class "Default")
      (node (ref "R125") (pin "1") (pinfunction "1_1") (pintype "passive"))
      (node (ref "U33") (pin "27") (pinfunction "BDBUS1_27") (pintype "bidirectional"))
    )
    (net (code "79") (name "Net-(U33-BDBUS2)") (class "Default")
      (node (ref "R126") (pin "1") (pinfunction "1_1") (pintype "passive"))
      (node (ref "U33") (pin "28") (pinfunction "BDBUS2_28") (pintype "bidirectional"))
    )
    (net (code "80") (name "Net-(U33-BDBUS3)") (class "Default")
      (node (ref "R270") (pin "1") (pinfunction "1_1") (pintype "passive"))
      (node (ref "U33") (pin "29") (pinfunction "BDBUS3_29") (pintype "bidirectional"))
    )
    (net (code "81") (name "Net-(U33-CDBUS0)") (class "Default")
      (node (ref "R130") (pin "1") (pinfunction "1_1") (pintype "passive"))
      (node (ref "U33") (pin "38") (pinfunction "CDBUS0_38") (pintype "bidirectional"))
    )
    (net (code "82") (name "Net-(U33-CDBUS1)") (class "Default")
      (node (ref "R131") (pin "1") (pinfunction "1_1") (pintype "passive"))
      (node (ref "U33") (pin "39") (pinfunction "CDBUS1_39") (pintype "bidirectional"))
    )
    (net (code "83") (name "Net-(U33-DDBUS0)") (class "Default")
      (node (ref "R135") (pin "1") (pinfunction "1_1") (pintype "passive"))
      (node (ref "U33") (pin "48") (pinfunction "DDBUS0_48") (pintype "bidirectional"))
    )
    (net (code "84") (name "Net-(U33-DDBUS1)") (class "Default")
      (node (ref "R136") (pin "1") (pinfunction "1_1") (pintype "passive"))
      (node (ref "U33") (pin "52") (pinfunction "DDBUS1_52") (pintype "bidirectional"))
    )
    (net (code "85") (name "Net-(U33-DDBUS3)") (class "Default")
      (node (ref "R243") (pin "1") (pinfunction "1_1") (pintype "passive"))
      (node (ref "U33") (pin "54") (pinfunction "DDBUS3_54") (pintype "bidirectional"))
    )
    (net (code "86") (name "Net-(U33-DDBUS4)") (class "Default")
      (node (ref "R138") (pin "1") (pinfunction "1_1") (pintype "passive"))
      (node (ref "U33") (pin "55") (pinfunction "DDBUS4_55") (pintype "bidirectional"))
    )
    (net (code "87") (name "Net-(U33-DDBUS5)") (class "Default")
      (node (ref "R139") (pin "1") (pinfunction "1_1") (pintype "passive"))
      (node (ref "U33") (pin "57") (pinfunction "DDBUS5_57") (pintype "bidirectional"))
    )
    (net (code "88") (name "Net-(U33-DDBUS6)") (class "Default")
      (node (ref "R226") (pin "1") (pinfunction "1_1") (pintype "passive"))
      (node (ref "U33") (pin "58") (pinfunction "DDBUS6_58") (pintype "bidirectional"))
    )
    (net (code "89") (name "Net-(U33-EECLK)") (class "Default")
      (node (ref "R132") (pin "1") (pinfunction "1_1") (pintype "passive"))
      (node (ref "U33") (pin "62") (pinfunction "EECLK_62") (pintype "passive"))
      (node (ref "U34") (pin "2") (pinfunction "CLK_2") (pintype "input"))
    )
    (net (code "90") (name "Net-(U33-EECS)") (class "Default")
      (node (ref "R133") (pin "1") (pinfunction "1_1") (pintype "passive"))
      (node (ref "U33") (pin "63") (pinfunction "EECS_63") (pintype "passive"))
      (node (ref "U34") (pin "1") (pinfunction "CS_1") (pintype "input"))
    )
    (net (code "91") (name "Net-(U33-EEDATA)") (class "Default")
      (node (ref "R137") (pin "2") (pinfunction "2_2") (pintype "passive"))
      (node (ref "U33") (pin "61") (pinfunction "EEDATA_61") (pintype "passive"))
      (node (ref "U34") (pin "3") (pinfunction "DI_3") (pintype "input"))
    )
    (net (code "92") (name "Net-(U33-OSCI)") (class "Default")
      (node (ref "C189") (pin "2") (pinfunction "2_2") (pintype "passive"))
      (node (ref "U33") (pin "2") (pinfunction "OSCI_2") (pintype "passive"))
      (node (ref "Y4") (pin "1") (pinfunction "1_1") (pintype "passive"))
    )
    (net (code "93") (name "Net-(U33-OSCO)") (class "Default")
      (node (ref "C190") (pin "2") (pinfunction "2_2") (pintype "passive"))
      (node (ref "U33") (pin "3") (pinfunction "OSCO_3") (pintype "passive"))
      (node (ref "Y4") (pin "3") (pinfunction "3_3") (pintype "passive"))
    )
    (net (code "94") (name "Net-(U33-REF)") (class "Default")
      (node (ref "R129") (pin "2") (pinfunction "2_2") (pintype "passive"))
      (node (ref "U33") (pin "6") (pinfunction "REF_6") (pintype "passive"))
    )
    (net (code "95") (name "Net-(U33-VPHY)") (class "Default")
      (node (ref "C177") (pin "2") (pinfunction "2_2") (pintype "passive"))
      (node (ref "C179") (pin "2") (pinfunction "2_2") (pintype "passive"))
      (node (ref "L19") (pin "2") (pinfunction "2_2") (pintype "passive"))
      (node (ref "U33") (pin "4") (pinfunction "VPHY_4") (pintype "passive"))
    )
    (net (code "96") (name "Net-(U33-VPLL)") (class "Default")
      (node (ref "C176") (pin "2") (pinfunction "2_2") (pintype "passive"))
      (node (ref "C178") (pin "2") (pinfunction "2_2") (pintype "passive"))
      (node (ref "L18") (pin "2") (pinfunction "2_2") (pintype "passive"))
      (node (ref "U33") (pin "9") (pinfunction "VPLL_9") (pintype "passive"))
    )
    (net (code "97") (name "Net-(U33-~{PWREN})") (class "Default")
      (node (ref "R61") (pin "1") (pinfunction "1_1") (pintype "passive"))
      (node (ref "U33") (pin "60") (pinfunction "~{PWREN}_60") (pintype "passive"))
    )
    (net (code "98") (name "Net-(U33-~{RESET})") (class "Default")
      (node (ref "R491") (pin "1") (pinfunction "1_1") (pintype "passive"))
      (node (ref "U33") (pin "14") (pinfunction "~{RESET}_14") (pintype "passive"))
    )
    (net (code "99") (name "Net-(U34-DO)") (class "Default")
      (node (ref "R134") (pin "1") (pinfunction "1_1") (pintype "passive"))
      (node (ref "R137") (pin "1") (pinfunction "1_1") (pintype "passive"))
      (node (ref "U34") (pin "4") (pinfunction "DO_4") (pintype "output"))
    )
    (net (code "100") (name "Net-(U36-C1N)") (class "Default")
      (node (ref "C193") (pin "2") (pinfunction "2_2") (pintype "passive"))
      (node (ref "U36") (pin "4") (pinfunction "C1N_4") (pintype "passive"))
    )
    (net (code "101") (name "Net-(U36-C1P)") (class "Default")
      (node (ref "C193") (pin "1") (pinfunction "1_1") (pintype "passive"))
      (node (ref "U36") (pin "2") (pinfunction "C1P_2") (pintype "passive"))
    )
    (net (code "102") (name "Net-(U36-C2N)") (class "Default")
      (node (ref "C194") (pin "2") (pinfunction "2_2") (pintype "passive"))
      (node (ref "U36") (pin "6") (pinfunction "C2N_6") (pintype "passive"))
    )
    (net (code "103") (name "Net-(U36-C2P)") (class "Default")
      (node (ref "C194") (pin "1") (pinfunction "1_1") (pintype "passive"))
      (node (ref "U36") (pin "5") (pinfunction "C2P_5") (pintype "passive"))
    )
    (net (code "104") (name "Net-(U36-FON)") (class "Default")
      (node (ref "U36") (pin "11") (pinfunction "INVALID#_11") (pintype "output"))
      (node (ref "U36") (pin "14") (pinfunction "FON_14") (pintype "input"))
    )
    (net (code "105") (name "Net-(U36-R1IN)") (class "Default")
      (node (ref "P6") (pin "3") (pinfunction "3_3") (pintype "passive"))
      (node (ref "U36") (pin "16") (pinfunction "R1IN_16") (pintype "input"))
    )
    (net (code "106") (name "Net-(U36-R2IN)") (class "Default")
      (node (ref "P6") (pin "5") (pinfunction "5_5") (pintype "passive"))
      (node (ref "U36") (pin "9") (pinfunction "R2IN_9") (pintype "input"))
    )
    (net (code "107") (name "Net-(U36-READY)") (class "Default")
      (node (ref "TP39") (pin "1") (pinfunction "1_1") (pintype "passive"))
      (node (ref "U36") (pin "1") (pinfunction "READY_1") (pintype "output"))
    )
    (net (code "108") (name "Net-(U36-T1OUT)") (class "Default")
      (node (ref "P6") (pin "2") (pinfunction "2_2") (pintype "passive"))
      (node (ref "U36") (pin "17") (pinfunction "T1OUT_17") (pintype "output"))
    )
    (net (code "109") (name "Net-(U36-T2OUT)") (class "Default")
      (node (ref "P6") (pin "4") (pinfunction "4_4") (pintype "passive"))
      (node (ref "U36") (pin "8") (pinfunction "T2OUT_8") (pintype "output"))
    )
    (net (code "110") (name "Net-(U36-V+)") (class "Default")
      (node (ref "C192") (pin "2") (pinfunction "2_2") (pintype "passive"))
      (node (ref "U36") (pin "3") (pinfunction "V+_3") (pintype "passive"))
    )
    (net (code "111") (name "Net-(U36-V-)") (class "Default")
      (node (ref "C195") (pin "2") (pinfunction "2_2") (pintype "passive"))
      (node (ref "U36") (pin "7") (pinfunction "V-_7") (pintype "passive"))
    )
    (net (code "112") (name "VBUS_FTDI") (class "Default")
      (node (ref "P3") (pin "1") (pinfunction "1_1") (pintype "power_in"))
      (node (ref "R127") (pin "1") (pinfunction "1_1") (pintype "passive"))
      (node (ref "VR1") (pin "2") (pinfunction "2_2") (pintype "passive"))
    )
    (net (code "113") (name "unconnected-(P6-Pad1)") (class "Default")
      (node (ref "P6") (pin "1") (pinfunction "1_1") (pintype "passive+no_connect"))
    )
    (net (code "114") (name "unconnected-(U2F-GPIO32{slash}USB2OM0-PadR3)") (class "Default")
      (node (ref "U2") (pin "R3") (pinfunction "GPIO32/USB2OM0_R3") (pintype "input+no_connect"))
    )
    (net (code "115") (name "unconnected-(U2F-GPIO33{slash}USB2OM1-PadR4)") (class "Default")
      (node (ref "U2") (pin "R4") (pinfunction "GPIO33/USB2OM1_R4") (pintype "input+no_connect"))
    )
    (net (code "116") (name "unconnected-(U2F-USB2CLK-PadA5)") (class "Default")
      (node (ref "U2") (pin "A5") (pinfunction "USB2CLK_A5") (pintype "output+no_connect"))
    )
    (net (code "117") (name "unconnected-(U2F-USB2LS0_DRVINH1-PadR2)") (class "Default")
      (node (ref "U2") (pin "R2") (pinfunction "USB2LS0_DRVINH1_R2") (pintype "output+no_connect"))
    )
    (net (code "118") (name "unconnected-(U2F-USB2LS1_LEAKTEST_HOLDPRI-PadP1)") (class "Default")
      (node (ref "U2") (pin "P1") (pinfunction "USB2LS1_LEAKTEST_HOLDPRI_P1") (pintype "output+no_connect"))
    )
    (net (code "119") (name "unconnected-(U2F-USB2RXACT_HOLDREQ_RCVINH-PadD7)") (class "Default")
      (node (ref "U2") (pin "D7") (pinfunction "USB2RXACT_HOLDREQ_RCVINH_D7") (pintype "output+no_connect"))
    )
    (net (code "120") (name "unconnected-(U2F-USB2RXVAL_LEAKTEST2-PadC8)") (class "Default")
      (node (ref "U2") (pin "C8") (pinfunction "USB2RXVAL_LEAKTEST2_C8") (pintype "output+no_connect"))
    )
    (net (code "121") (name "unconnected-(U2F-USB2TXRDY_REFEN-PadB6)") (class "Default")
      (node (ref "U2") (pin "B6") (pinfunction "USB2TXRDY_REFEN_B6") (pintype "output+no_connect"))
    )
    (net (code "122") (name "unconnected-(U33-ADBUS5-Pad22)") (class "Default")
      (node (ref "U33") (pin "22") (pinfunction "ADBUS5_22") (pintype "bidirectional+no_connect"))
    )
    (net (code "123") (name "unconnected-(U33-ADBUS6-Pad23)") (class "Default")
      (node (ref "U33") (pin "23") (pinfunction "ADBUS6_23") (pintype "bidirectional+no_connect"))
    )
    (net (code "124") (name "unconnected-(U33-ADBUS7-Pad24)") (class "Default")
      (node (ref "U33") (pin "24") (pinfunction "ADBUS7_24") (pintype "bidirectional+no_connect"))
    )
    (net (code "125") (name "unconnected-(U33-CDBUS2-Pad40)") (class "Default")
      (node (ref "U33") (pin "40") (pinfunction "CDBUS2_40") (pintype "bidirectional+no_connect"))
    )
    (net (code "126") (name "unconnected-(U33-CDBUS3-Pad41)") (class "Default")
      (node (ref "U33") (pin "41") (pinfunction "CDBUS3_41") (pintype "bidirectional+no_connect"))
    )
    (net (code "127") (name "unconnected-(U33-CDBUS4-Pad43)") (class "Default")
      (node (ref "U33") (pin "43") (pinfunction "CDBUS4_43") (pintype "bidirectional"))
    )
    (net (code "128") (name "unconnected-(U33-CDBUS5-Pad44)") (class "Default")
      (node (ref "U33") (pin "44") (pinfunction "CDBUS5_44") (pintype "bidirectional"))
    )
    (net (code "129") (name "unconnected-(U33-CDBUS6-Pad45)") (class "Default")
      (node (ref "U33") (pin "45") (pinfunction "CDBUS6_45") (pintype "bidirectional+no_connect"))
    )
    (net (code "130") (name "unconnected-(U33-CDBUS7-Pad46)") (class "Default")
      (node (ref "U33") (pin "46") (pinfunction "CDBUS7_46") (pintype "bidirectional+no_connect"))
    )
    (net (code "131") (name "unconnected-(U33-DDBUS2-Pad53)") (class "Default")
      (node (ref "U33") (pin "53") (pinfunction "DDBUS2_53") (pintype "bidirectional+no_connect"))
    )
    (net (code "132") (name "unconnected-(U33-DDBUS7-Pad59)") (class "Default")
      (node (ref "U33") (pin "59") (pinfunction "DDBUS7_59") (pintype "bidirectional+no_connect"))
    )
    (net (code "133") (name "unconnected-(U33-~{SUSPEND}-Pad36)") (class "Default")
      (node (ref "U33") (pin "36") (pinfunction "~{SUSPEND}_36") (pintype "passive+no_connect"))
    )
    (net (code "134") (name "unconnected-(U34-NU-Pad7)") (class "Default")
      (node (ref "U34") (pin "7") (pinfunction "NU_7") (pintype "power_in+no_connect"))
    )
    (net (code "135") (name "unconnected-(U34-ORG-Pad6)") (class "Default")
      (node (ref "U34") (pin "6") (pinfunction "ORG_6") (pintype "power_in+no_connect"))
    )
    (net (code "136") (name "unconnected-(U87-B1-Pad1)") (class "Default")
      (node (ref "U87") (pin "1") (pinfunction "B1_1") (pintype "passive+no_connect"))
    )
    (net (code "137") (name "unconnected-(U89-B1-Pad1)") (class "Default")
      (node (ref "U89") (pin "1") (pinfunction "B1_1") (pintype "passive+no_connect"))
    )
    (net (code "138") (name "unconnected-(Y3-Pad2)") (class "Default")
      (node (ref "Y3") (pin "2") (pinfunction "2_2") (pintype "passive"))
    )
    (net (code "139") (name "unconnected-(Y3-Pad2)_1") (class "Default")
      (node (ref "Y3") (pin "2") (pinfunction "2_2") (pintype "passive"))
    )
    (net (code "140") (name "unconnected-(Y3-Pad3)") (class "Default")
      (node (ref "Y3") (pin "3") (pinfunction "3_3") (pintype "passive"))
    )
    (net (code "141") (name "unconnected-(Y3-Pad4)") (class "Default")
      (node (ref "Y3") (pin "4") (pinfunction "4_4") (pintype "passive"))
    )
    (net (code "142") (name "unconnected-(Y4-Pad2)") (class "Default")
      (node (ref "Y4") (pin "2") (pinfunction "2_2") (pintype "passive"))
    )
    (net (code "143") (name "unconnected-(Y4-Pad2)_1") (class "Default")
      (node (ref "Y4") (pin "2") (pinfunction "2_2") (pintype "passive"))
    )
    (net (code "144") (name "unconnected-(Y4-Pad3)") (class "Default")
      (node (ref "Y4") (pin "3") (pinfunction "3_3") (pintype "passive"))
    )
    (net (code "145") (name "unconnected-(Y4-Pad4)") (class "Default")
      (node (ref "Y4") (pin "4") (pinfunction "4_4") (pintype "passive"))
    )
  )
)
